# CHM_CPU_FPGA_EX.net
KiCad netlist of a schematic drawn in Altium Designer
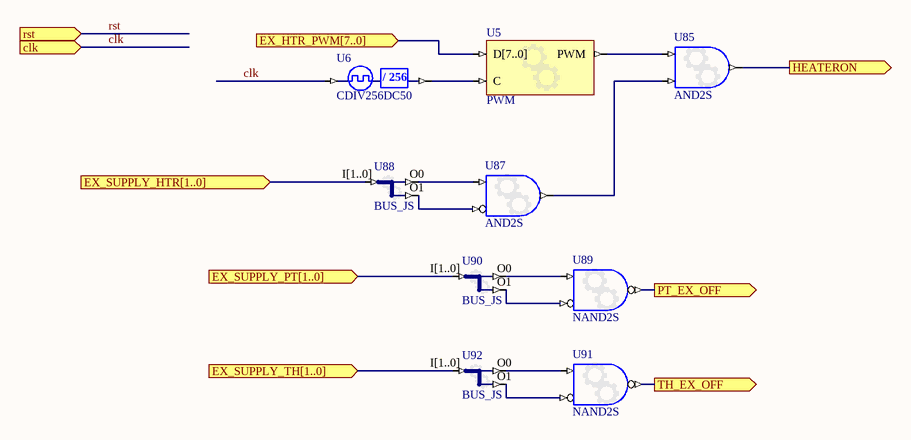
[diagram p0: CHM_CPU_FPGA_EX.SchDoc]

(export (version "E")
  (design (tool "Eeschema 10.0.6"))
  (components
    (comp (ref "U5")
      (value "PWM")
      (description "Configurable PWM")
      (fields (field (name "PUBLISHER") "Altium Limited"))
      (libsource (lib "FPGA Configurable Generic") (part "PWM"))
    )
    (comp (ref "U6")
      (value "CDIV256DC50")
      (description "Clock Divider by 256 with 50% Duty Cycle Output")
      (fields (field (name "PUBLISHER") "Altium Limited"))
      (libsource (lib "FPGA Generic") (part "CDIV256DC50"))
    )
    (comp (ref "U85")
      (value "AND2S")
      (description "Configurable Generic Gate")
      (fields (field (name "PUBLISHER") "Altium Limited"))
      (libsource (lib "FPGA Configurable Generic") (part "GATE"))
    )
    (comp (ref "U87")
      (value "AND2S")
      (description "Configurable Generic Gate")
      (fields (field (name "PUBLISHER") "Altium Limited"))
      (libsource (lib "FPGA Configurable Generic") (part "GATE"))
    )
    (comp (ref "U88")
      (value "BUS_JS")
      (description "Configurable Bus Joiner/Splitter")
      (fields (field (name "PUBLISHER") "Altium Limited"))
      (libsource (lib "FPGA Configurable Generic") (part "BUS_JS"))
    )
    (comp (ref "U89")
      (value "NAND2S")
      (description "Configurable Generic Gate")
      (fields (field (name "PUBLISHER") "Altium Limited"))
      (libsource (lib "FPGA Configurable Generic") (part "GATE"))
    )
    (comp (ref "U90")
      (value "BUS_JS")
      (description "Configurable Bus Joiner/Splitter")
      (fields (field (name "PUBLISHER") "Altium Limited"))
      (libsource (lib "FPGA Configurable Generic") (part "BUS_JS"))
    )
    (comp (ref "U91")
      (value "NAND2S")
      (description "Configurable Generic Gate")
      (fields (field (name "PUBLISHER") "Altium Limited"))
      (libsource (lib "FPGA Configurable Generic") (part "GATE"))
    )
    (comp (ref "U92")
      (value "BUS_JS")
      (description "Configurable Bus Joiner/Splitter")
      (fields (field (name "PUBLISHER") "Altium Limited"))
      (libsource (lib "FPGA Configurable Generic") (part "BUS_JS"))
    )
  )
  (nets
    (net (code "15") (name "/EX_HTR_PWM[7..0]") (class "Default")
      (node (ref "U5") (pin "D[7..0]") (pinfunction "D[7..0]_D[7..0]") (pintype "input"))
    )
    (net (code "16") (name "/EX_SUPPLY_HTR[1..0]") (class "Default")
      (node (ref "U88") (pin "I[1..0]") (pinfunction "I[1..0]_I[1..0]") (pintype "input"))
    )
    (net (code "17") (name "/EX_SUPPLY_PT[1..0]") (class "Default")
      (node (ref "U90") (pin "I[1..0]") (pinfunction "I[1..0]_I[1..0]") (pintype "input"))
    )
    (net (code "18") (name "/EX_SUPPLY_TH[1..0]") (class "Default")
      (node (ref "U92") (pin "I[1..0]") (pinfunction "I[1..0]_I[1..0]") (pintype "input"))
    )
    (net (code "19") (name "/HEATERON") (class "Default")
      (node (ref "U85") (pin "O") (pinfunction "O_O") (pintype "output"))
    )
    (net (code "20") (name "/PT_EX_OFF") (class "Default")
      (node (ref "U89") (pin "O") (pinfunction "O_O") (pintype "output"))
    )
    (net (code "21") (name "/TH_EX_OFF") (class "Default")
      (node (ref "U91") (pin "O") (pinfunction "O_O") (pintype "output"))
    )
    (net (code "22") (name "/clk") (class "Default")
      (node (ref "U6") (pin "CLKIN") (pinfunction "CLKIN_CLKIN") (pintype "input"))
    )
    (net (code "24") (name "Net-(U5-PadC)") (class "Default")
      (node (ref "U5") (pin "C") (pinfunction "C_C") (pintype "input"))
      (node (ref "U6") (pin "CLKDV") (pinfunction "CLKDV_CLKDV") (pintype "output"))
    )
    (net (code "25") (name "Net-(U5-PadPWM)") (class "Default")
      (node (ref "U5") (pin "PWM") (pinfunction "PWM_PWM") (pintype "output"))
      (node (ref "U85") (pin "I0") (pinfunction "I0_I0") (pintype "input"))
    )
    (net (code "26") (name "Net-(U85-PadI1)") (class "Default")
      (node (ref "U85") (pin "I1") (pinfunction "I1_I1") (pintype "input"))
      (node (ref "U87") (pin "O") (pinfunction "O_O") (pintype "output"))
    )
    (net (code "27") (name "Net-(U87-PadI0)") (class "Default")
      (node (ref "U87") (pin "I0") (pinfunction "I0_I0") (pintype "input"))
      (node (ref "U88") (pin "O0") (pinfunction "O0_O0") (pintype "output"))
    )
    (net (code "28") (name "Net-(U87-PadI1)") (class "Default")
      (node (ref "U87") (pin "I1") (pinfunction "I1_I1") (pintype "input"))
      (node (ref "U88") (pin "O1") (pinfunction "O1_O1") (pintype "output"))
    )
    (net (code "29") (name "Net-(U89-PadI0)") (class "Default")
      (node (ref "U89") (pin "I0") (pinfunction "I0_I0") (pintype "input"))
      (node (ref "U90") (pin "O0") (pinfunction "O0_O0") (pintype "output"))
    )
    (net (code "30") (name "Net-(U89-PadI1)") (class "Default")
      (node (ref "U89") (pin "I1") (pinfunction "I1_I1") (pintype "input"))
      (node (ref "U90") (pin "O1") (pinfunction "O1_O1") (pintype "output"))
    )
    (net (code "31") (name "Net-(U91-PadI0)") (class "Default")
      (node (ref "U91") (pin "I0") (pinfunction "I0_I0") (pintype "input"))
      (node (ref "U92") (pin "O0") (pinfunction "O0_O0") (pintype "output"))
    )
    (net (code "32") (name "Net-(U91-PadI1)") (class "Default")
      (node (ref "U91") (pin "I1") (pinfunction "I1_I1") (pintype "input"))
      (node (ref "U92") (pin "O1") (pinfunction "O1_O1") (pintype "output"))
    )
  )
)
